# AC-DC-5V-_Regulator.net
KiCad netlist of a schematic drawn in EAGLE
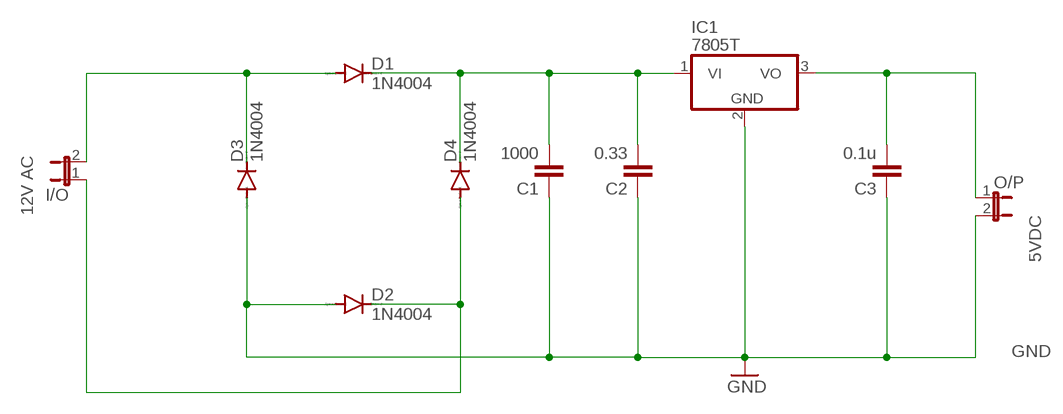
[diagram p0: schematic, sheet 1]

(export (version "E")
  (design (tool "Eeschema 10.0.6"))
  (components
    (comp (ref "C1")
      (value "1000")
      (footprint "eagle-import:C2.5-3")
      (libsource (lib "eagle-import") (part "C2,5-3"))
    )
    (comp (ref "C2")
      (value "0.33")
      (footprint "eagle-import:C2.5-3")
      (libsource (lib "eagle-import") (part "C2,5-3"))
    )
    (comp (ref "C3")
      (value "0.1u")
      (footprint "eagle-import:C2.5-3")
      (libsource (lib "eagle-import") (part "C2,5-3"))
    )
    (comp (ref "D1")
      (value "1N4004")
      (footprint "eagle-import:DO41-10")
      (libsource (lib "eagle-import") (part "1N4004"))
    )
    (comp (ref "D2")
      (value "1N4004")
      (footprint "eagle-import:DO41-10")
      (libsource (lib "eagle-import") (part "1N4004"))
    )
    (comp (ref "D3")
      (value "1N4004")
      (footprint "eagle-import:DO41-10")
      (libsource (lib "eagle-import") (part "1N4004"))
    )
    (comp (ref "D4")
      (value "1N4004")
      (footprint "eagle-import:DO41-10")
      (libsource (lib "eagle-import") (part "1N4004"))
    )
    (comp (ref "I/O")
      (value "JP1E")
      (footprint "eagle-import:JP1")
      (fields (field (name "POPULARITY") "61") (field (name "POPULARITY_1") "12V AC"))
      (libsource (lib "eagle-import") (part "JP1E"))
    )
    (comp (ref "IC1")
      (value "7805T")
      (footprint "eagle-import:TO220H")
      (libsource (lib "eagle-import") (part "78T05"))
    )
    (comp (ref "O/P")
      (value "JP1E")
      (footprint "eagle-import:JP1")
      (fields (field (name "POPULARITY") "61") (field (name "POPULARITY_1") "5VDC"))
      (libsource (lib "eagle-import") (part "JP1E"))
    )
  )
  (nets
    (net (code "1") (name "GND") (class "Default")
      (node (ref "C1") (pin "1") (pinfunction "1_1") (pintype "passive"))
      (node (ref "C2") (pin "1") (pinfunction "1_1") (pintype "passive"))
      (node (ref "C3") (pin "1") (pinfunction "1_1") (pintype "passive"))
      (node (ref "D2") (pin "A") (pinfunction "A_A") (pintype "passive"))
      (node (ref "D3") (pin "A") (pinfunction "A_A") (pintype "passive"))
      (node (ref "IC1") (pin "2") (pinfunction "GND_2") (pintype "passive"))
      (node (ref "O/P") (pin "2") (pinfunction "2_2") (pintype "passive"))
    )
    (net (code "2") (name "Net-(D1-PadA)") (class "Default")
      (node (ref "D1") (pin "A") (pinfunction "A_A") (pintype "passive"))
      (node (ref "D3") (pin "C") (pinfunction "C_C") (pintype "passive"))
      (node (ref "I/O") (pin "2") (pinfunction "2_2") (pintype "passive"))
    )
    (net (code "3") (name "Net-(D2-PadC)") (class "Default")
      (node (ref "D2") (pin "C") (pinfunction "C_C") (pintype "passive"))
      (node (ref "D4") (pin "A") (pinfunction "A_A") (pintype "passive"))
      (node (ref "I/O") (pin "1") (pinfunction "1_1") (pintype "passive"))
    )
    (net (code "4") (name "Net-(IC1-VI)") (class "Default")
      (node (ref "C1") (pin "2") (pinfunction "2_2") (pintype "passive"))
      (node (ref "C2") (pin "2") (pinfunction "2_2") (pintype "passive"))
      (node (ref "D1") (pin "C") (pinfunction "C_C") (pintype "passive"))
      (node (ref "D4") (pin "C") (pinfunction "C_C") (pintype "passive"))
      (node (ref "IC1") (pin "1") (pinfunction "VI_1") (pintype "input"))
    )
    (net (code "5") (name "Net-(IC1-VO)") (class "Default")
      (node (ref "C3") (pin "2") (pinfunction "2_2") (pintype "passive"))
      (node (ref "IC1") (pin "3") (pinfunction "VO_3") (pintype "passive"))
      (node (ref "O/P") (pin "1") (pinfunction "1_1") (pintype "passive"))
    )
  )
)
